# flipdot.net
KiCad netlist of a schematic drawn in EAGLE
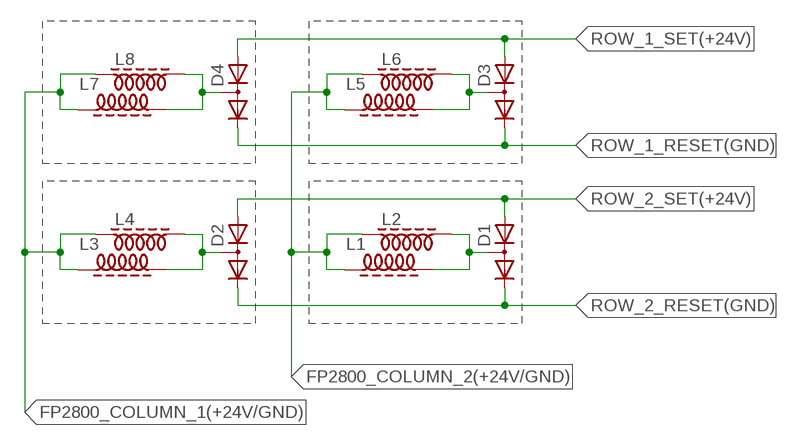
[diagram p0: schematic, sheet 1]

(export (version "E")
  (design (tool "Eeschema 10.0.6"))
  (components
    (comp (ref "D1")
      (value "DIODE_2CACA-SOT23")
      (footprint "eagle-import:SOT23")
      (libsource (lib "eagle-import") (part "DIODE_2CACA-SOT23"))
    )
    (comp (ref "D2")
      (value "DIODE_2CACA-SOT23")
      (footprint "eagle-import:SOT23")
      (libsource (lib "eagle-import") (part "DIODE_2CACA-SOT23"))
    )
    (comp (ref "D3")
      (value "DIODE_2CACA-SOT23")
      (footprint "eagle-import:SOT23")
      (libsource (lib "eagle-import") (part "DIODE_2CACA-SOT23"))
    )
    (comp (ref "D4")
      (value "DIODE_2CACA-SOT23")
      (footprint "eagle-import:SOT23")
      (libsource (lib "eagle-import") (part "DIODE_2CACA-SOT23"))
    )
    (comp (ref "L1")
      (value "Z14/40CCW")
      (footprint "eagle-import:Z15_4")
      (libsource (lib "eagle-import") (part "Z?CCW14/40"))
    )
    (comp (ref "L2")
      (value "Z4/150CW")
      (footprint "eagle-import:Z4_15")
      (libsource (lib "eagle-import") (part "Z?CW4/150"))
    )
    (comp (ref "L3")
      (value "Z14/40CCW")
      (footprint "eagle-import:Z15_4")
      (libsource (lib "eagle-import") (part "Z?CCW14/40"))
    )
    (comp (ref "L4")
      (value "Z4/150CW")
      (footprint "eagle-import:Z4_15")
      (libsource (lib "eagle-import") (part "Z?CW4/150"))
    )
    (comp (ref "L5")
      (value "Z14/40CCW")
      (footprint "eagle-import:Z15_4")
      (libsource (lib "eagle-import") (part "Z?CCW14/40"))
    )
    (comp (ref "L6")
      (value "Z4/150CW")
      (footprint "eagle-import:Z4_15")
      (libsource (lib "eagle-import") (part "Z?CW4/150"))
    )
    (comp (ref "L7")
      (value "Z14/40CCW")
      (footprint "eagle-import:Z15_4")
      (libsource (lib "eagle-import") (part "Z?CCW14/40"))
    )
    (comp (ref "L8")
      (value "Z4/150CW")
      (footprint "eagle-import:Z4_15")
      (libsource (lib "eagle-import") (part "Z?CW4/150"))
    )
  )
  (nets
    (net (code "1") (name "FP2800_COLUMN_1(+24V{slash}GND)") (class "Default")
      (node (ref "L3") (pin "1") (pinfunction "1_1") (pintype "passive"))
      (node (ref "L4") (pin "1") (pinfunction "1_1") (pintype "passive"))
      (node (ref "L7") (pin "1") (pinfunction "1_1") (pintype "passive"))
      (node (ref "L8") (pin "1") (pinfunction "1_1") (pintype "passive"))
    )
    (net (code "2") (name "FP2800_COLUMN_2(+24V{slash}GND)") (class "Default")
      (node (ref "L1") (pin "1") (pinfunction "1_1") (pintype "passive"))
      (node (ref "L2") (pin "1") (pinfunction "1_1") (pintype "passive"))
      (node (ref "L5") (pin "1") (pinfunction "1_1") (pintype "passive"))
      (node (ref "L6") (pin "1") (pinfunction "1_1") (pintype "passive"))
    )
    (net (code "3") (name "Net-(D1-AC)") (class "Default")
      (node (ref "D1") (pin "3") (pinfunction "AC_3") (pintype "passive"))
      (node (ref "L1") (pin "2") (pinfunction "2_2") (pintype "passive"))
      (node (ref "L2") (pin "2") (pinfunction "2_2") (pintype "passive"))
    )
    (net (code "4") (name "Net-(D2-AC)") (class "Default")
      (node (ref "D2") (pin "3") (pinfunction "AC_3") (pintype "passive"))
      (node (ref "L3") (pin "2") (pinfunction "2_2") (pintype "passive"))
      (node (ref "L4") (pin "2") (pinfunction "2_2") (pintype "passive"))
    )
    (net (code "5") (name "Net-(D3-AC)") (class "Default")
      (node (ref "D3") (pin "3") (pinfunction "AC_3") (pintype "passive"))
      (node (ref "L5") (pin "2") (pinfunction "2_2") (pintype "passive"))
      (node (ref "L6") (pin "2") (pinfunction "2_2") (pintype "passive"))
    )
    (net (code "6") (name "Net-(D4-AC)") (class "Default")
      (node (ref "D4") (pin "3") (pinfunction "AC_3") (pintype "passive"))
      (node (ref "L7") (pin "2") (pinfunction "2_2") (pintype "passive"))
      (node (ref "L8") (pin "2") (pinfunction "2_2") (pintype "passive"))
    )
    (net (code "7") (name "ROW_1_RESET(GND)") (class "Default")
      (node (ref "D3") (pin "2") (pinfunction "C_2") (pintype "passive"))
      (node (ref "D4") (pin "2") (pinfunction "C_2") (pintype "passive"))
    )
    (net (code "8") (name "ROW_1_SET(+24V)") (class "Default")
      (node (ref "D3") (pin "1") (pinfunction "A_1") (pintype "passive"))
      (node (ref "D4") (pin "1") (pinfunction "A_1") (pintype "passive"))
    )
    (net (code "9") (name "ROW_2_RESET(GND)") (class "Default")
      (node (ref "D1") (pin "2") (pinfunction "C_2") (pintype "passive"))
      (node (ref "D2") (pin "2") (pinfunction "C_2") (pintype "passive"))
    )
    (net (code "10") (name "ROW_2_SET(+24V)") (class "Default")
      (node (ref "D1") (pin "1") (pinfunction "A_1") (pintype "passive"))
      (node (ref "D2") (pin "1") (pinfunction "A_1") (pintype "passive"))
    )
  )
)
